# power-supply_pos_v1.net
KiCad netlist of a schematic drawn in EAGLE
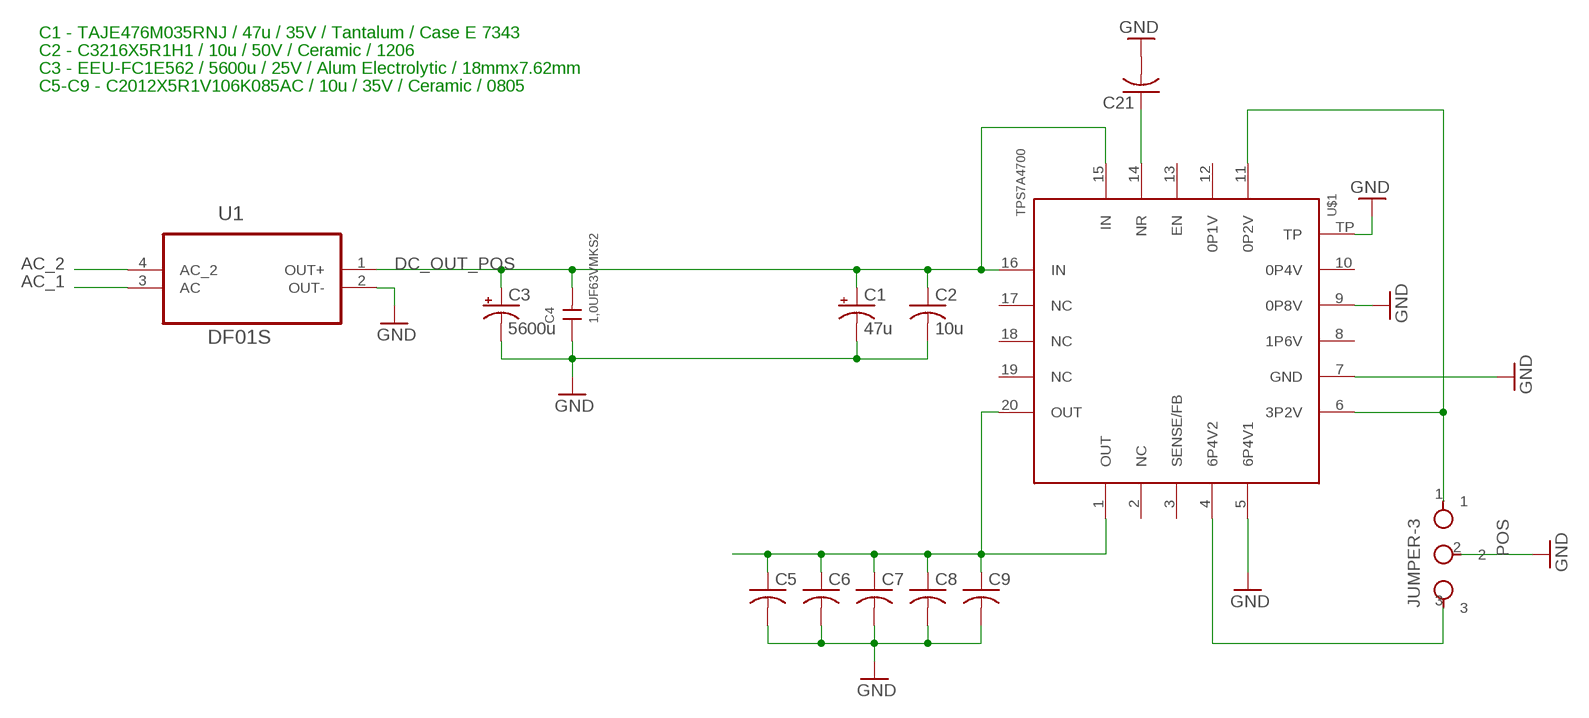
[diagram p0: schematic, sheet 1]
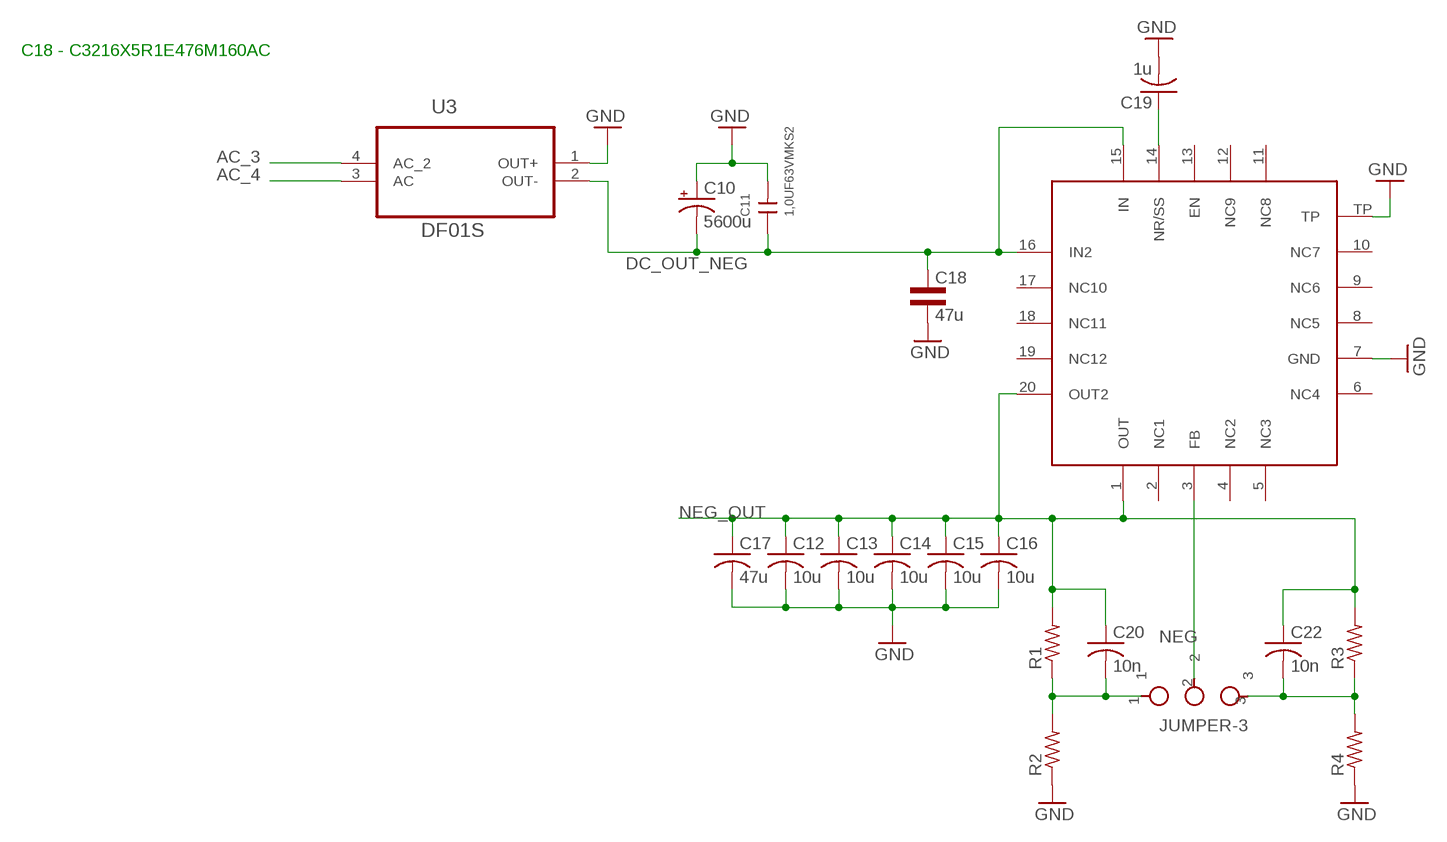
[diagram p1: schematic, sheet 2]

(export (version "E")
  (design (tool "Eeschema 10.0.6"))
  (components
    (comp (ref "C1")
      (value "47u")
      (footprint "eagle-import:SMC_E")
      (libsource (lib "eagle-import") (part "CPOL-USSMCE"))
    )
    (comp (ref "C2")
      (value "10u")
      (footprint "eagle-import:C1206")
      (libsource (lib "eagle-import") (part "C-USC1206"))
    )
    (comp (ref "C3")
      (value "5600u")
      (footprint "eagle-import:E7,5-18")
      (libsource (lib "eagle-import") (part "CPOL-USE7.5-18"))
    )
    (comp (ref "C4")
      (value "1,0UF63VMKS2")
      (footprint "eagle-import:5,0X10,0RM5,0")
      (libsource (lib "eagle-import") (part "1,0UF63VMKS2"))
    )
    (comp (ref "C5")
      (value "C-USC0805")
      (footprint "eagle-import:C0805")
      (libsource (lib "eagle-import") (part "C-USC0805"))
    )
    (comp (ref "C6")
      (value "C-USC0805")
      (footprint "eagle-import:C0805")
      (libsource (lib "eagle-import") (part "C-USC0805"))
    )
    (comp (ref "C7")
      (value "C-USC0805")
      (footprint "eagle-import:C0805")
      (libsource (lib "eagle-import") (part "C-USC0805"))
    )
    (comp (ref "C8")
      (value "C-USC0805")
      (footprint "eagle-import:C0805")
      (libsource (lib "eagle-import") (part "C-USC0805"))
    )
    (comp (ref "C9")
      (value "C-USC0805")
      (footprint "eagle-import:C0805")
      (libsource (lib "eagle-import") (part "C-USC0805"))
    )
    (comp (ref "C21")
      (value "C-USC0603")
      (footprint "eagle-import:C0603")
      (libsource (lib "eagle-import") (part "C-USC0603"))
    )
    (comp (ref "POS")
      (value "JUMPER-3")
      (footprint "eagle-import:1X03")
      (libsource (lib "eagle-import") (part "JUMPER-3"))
    )
    (comp (ref "U$1")
      (value "TPS7A4700")
      (footprint "eagle-import:VQFN-20")
      (libsource (lib "eagle-import") (part "TPS7A4700"))
    )
    (comp (ref "U1")
      (value "DF01S")
      (footprint "eagle-import:SOT508P985X260-4N")
      (libsource (lib "eagle-import") (part "DF01S"))
    )
    (comp (ref "C10")
      (value "5600u")
      (footprint "eagle-import:E7,5-18")
      (libsource (lib "eagle-import") (part "CPOL-USE7.5-18"))
    )
    (comp (ref "C11")
      (value "1,0UF63VMKS2")
      (footprint "eagle-import:5,0X10,0RM5,0")
      (libsource (lib "eagle-import") (part "1,0UF63VMKS2"))
    )
    (comp (ref "C12")
      (value "10u")
      (footprint "eagle-import:C0805")
      (libsource (lib "eagle-import") (part "C-USC0805"))
    )
    (comp (ref "C13")
      (value "10u")
      (footprint "eagle-import:C0805")
      (libsource (lib "eagle-import") (part "C-USC0805"))
    )
    (comp (ref "C14")
      (value "10u")
      (footprint "eagle-import:C0805")
      (libsource (lib "eagle-import") (part "C-USC0805"))
    )
    (comp (ref "C15")
      (value "10u")
      (footprint "eagle-import:C0805")
      (libsource (lib "eagle-import") (part "C-USC0805"))
    )
    (comp (ref "C16")
      (value "10u")
      (footprint "eagle-import:C0805")
      (libsource (lib "eagle-import") (part "C-USC0805"))
    )
    (comp (ref "C17")
      (value "47u")
      (footprint "eagle-import:C2220K")
      (libsource (lib "eagle-import") (part "C-USC2220K"))
    )
    (comp (ref "C18")
      (value "47u")
      (footprint "eagle-import:1206L3")
      (libsource (lib "eagle-import") (part "CAP1206L3"))
    )
    (comp (ref "C19")
      (value "1u")
      (footprint "eagle-import:C0603")
      (libsource (lib "eagle-import") (part "C-USC0603"))
    )
    (comp (ref "C20")
      (value "10n")
      (footprint "eagle-import:C0603")
      (libsource (lib "eagle-import") (part "C-USC0603"))
    )
    (comp (ref "C22")
      (value "10n")
      (footprint "eagle-import:C0603")
      (libsource (lib "eagle-import") (part "C-USC0603"))
    )
    (comp (ref "NEG")
      (value "JUMPER-3")
      (footprint "eagle-import:1X03")
      (libsource (lib "eagle-import") (part "JUMPER-3"))
    )
    (comp (ref "R1")
      (value "R-US_R0603")
      (footprint "eagle-import:R0603")
      (libsource (lib "eagle-import") (part "R-US_R0603"))
    )
    (comp (ref "R2")
      (value "R-US_R0603")
      (footprint "eagle-import:R0603")
      (libsource (lib "eagle-import") (part "R-US_R0603"))
    )
    (comp (ref "R3")
      (value "R-US_R0603")
      (footprint "eagle-import:R0603")
      (libsource (lib "eagle-import") (part "R-US_R0603"))
    )
    (comp (ref "R4")
      (value "R-US_R0603")
      (footprint "eagle-import:R0603")
      (libsource (lib "eagle-import") (part "R-US_R0603"))
    )
    (comp (ref "U$2")
      (value "TPS7A3301RGWT")
      (footprint "eagle-import:VQFN-20")
      (libsource (lib "eagle-import") (part "TPS7A3301RGWT"))
    )
    (comp (ref "U3")
      (value "DF01S")
      (footprint "eagle-import:SOT508P985X260-4N")
      (libsource (lib "eagle-import") (part "DF01S"))
    )
  )
  (nets
    (net (code "1") (name "AC_1") (class "Default")
      (node (ref "U1") (pin "3") (pinfunction "AC_3") (pintype "input"))
    )
    (net (code "2") (name "AC_2") (class "Default")
      (node (ref "U1") (pin "4") (pinfunction "AC_2_4") (pintype "input"))
    )
    (net (code "3") (name "AC_3") (class "Default")
      (node (ref "U3") (pin "4") (pinfunction "AC_2_4") (pintype "input"))
    )
    (net (code "4") (name "AC_4") (class "Default")
      (node (ref "U3") (pin "3") (pinfunction "AC_3") (pintype "input"))
    )
    (net (code "5") (name "DC_OUT_NEG") (class "Default")
      (node (ref "C10") (pin "-") (pinfunction "-_-") (pintype "passive"))
      (node (ref "C11") (pin "1") (pinfunction "1_1") (pintype "passive"))
      (node (ref "C18") (pin "1") (pinfunction "1_1") (pintype "bidirectional"))
      (node (ref "U$2") (pin "15") (pinfunction "IN_15") (pintype "bidirectional"))
      (node (ref "U$2") (pin "16") (pinfunction "IN2_16") (pintype "bidirectional"))
      (node (ref "U3") (pin "2") (pinfunction "OUT-_2") (pintype "output"))
    )
    (net (code "6") (name "DC_OUT_POS") (class "Default")
      (node (ref "C1") (pin "+") (pinfunction "+_+") (pintype "passive"))
      (node (ref "C2") (pin "1") (pinfunction "1_1") (pintype "passive"))
      (node (ref "C3") (pin "+") (pinfunction "+_+") (pintype "passive"))
      (node (ref "C4") (pin "2") (pinfunction "2_2") (pintype "passive"))
      (node (ref "U$1") (pin "15") (pinfunction "IN_15") (pintype "bidirectional"))
      (node (ref "U$1") (pin "16") (pinfunction "IN_16") (pintype "bidirectional"))
      (node (ref "U1") (pin "1") (pinfunction "OUT+_1") (pintype "output"))
    )
    (net (code "7") (name "GND") (class "Default")
      (node (ref "C1") (pin "-") (pinfunction "-_-") (pintype "passive"))
      (node (ref "C10") (pin "+") (pinfunction "+_+") (pintype "passive"))
      (node (ref "C11") (pin "2") (pinfunction "2_2") (pintype "passive"))
      (node (ref "C12") (pin "2") (pinfunction "2_2") (pintype "passive"))
      (node (ref "C13") (pin "2") (pinfunction "2_2") (pintype "passive"))
      (node (ref "C14") (pin "2") (pinfunction "2_2") (pintype "passive"))
      (node (ref "C15") (pin "2") (pinfunction "2_2") (pintype "passive"))
      (node (ref "C16") (pin "2") (pinfunction "2_2") (pintype "passive"))
      (node (ref "C17") (pin "2") (pinfunction "2_2") (pintype "passive"))
      (node (ref "C18") (pin "2") (pinfunction "2_2") (pintype "bidirectional"))
      (node (ref "C19") (pin "2") (pinfunction "2_2") (pintype "passive"))
      (node (ref "C2") (pin "2") (pinfunction "2_2") (pintype "passive"))
      (node (ref "C21") (pin "2") (pinfunction "2_2") (pintype "passive"))
      (node (ref "C3") (pin "-") (pinfunction "-_-") (pintype "passive"))
      (node (ref "C4") (pin "1") (pinfunction "1_1") (pintype "passive"))
      (node (ref "C5") (pin "2") (pinfunction "2_2") (pintype "passive"))
      (node (ref "C6") (pin "2") (pinfunction "2_2") (pintype "passive"))
      (node (ref "C7") (pin "2") (pinfunction "2_2") (pintype "passive"))
      (node (ref "C8") (pin "2") (pinfunction "2_2") (pintype "passive"))
      (node (ref "C9") (pin "2") (pinfunction "2_2") (pintype "passive"))
      (node (ref "POS") (pin "2") (pinfunction "2_2") (pintype "bidirectional"))
      (node (ref "R2") (pin "1") (pinfunction "1_1") (pintype "passive"))
      (node (ref "R4") (pin "1") (pinfunction "1_1") (pintype "passive"))
      (node (ref "U$1") (pin "5") (pinfunction "6P4V1_5") (pintype "bidirectional"))
      (node (ref "U$1") (pin "7") (pinfunction "GND_7") (pintype "bidirectional"))
      (node (ref "U$1") (pin "9") (pinfunction "0P8V_9") (pintype "bidirectional"))
      (node (ref "U$1") (pin "TP") (pinfunction "TP_TP") (pintype "bidirectional"))
      (node (ref "U$2") (pin "7") (pinfunction "GND_7") (pintype "bidirectional"))
      (node (ref "U$2") (pin "TP") (pinfunction "TP_TP") (pintype "bidirectional"))
      (node (ref "U1") (pin "2") (pinfunction "OUT-_2") (pintype "output"))
      (node (ref "U3") (pin "1") (pinfunction "OUT+_1") (pintype "output"))
    )
    (net (code "8") (name "NEG_OUT") (class "Default")
      (node (ref "C12") (pin "1") (pinfunction "1_1") (pintype "passive"))
      (node (ref "C13") (pin "1") (pinfunction "1_1") (pintype "passive"))
      (node (ref "C14") (pin "1") (pinfunction "1_1") (pintype "passive"))
      (node (ref "C15") (pin "1") (pinfunction "1_1") (pintype "passive"))
      (node (ref "C16") (pin "1") (pinfunction "1_1") (pintype "passive"))
      (node (ref "C17") (pin "1") (pinfunction "1_1") (pintype "passive"))
      (node (ref "C20") (pin "1") (pinfunction "1_1") (pintype "passive"))
      (node (ref "C22") (pin "1") (pinfunction "1_1") (pintype "passive"))
      (node (ref "R1") (pin "2") (pinfunction "2_2") (pintype "passive"))
      (node (ref "R3") (pin "2") (pinfunction "2_2") (pintype "passive"))
      (node (ref "U$2") (pin "1") (pinfunction "OUT_1") (pintype "bidirectional"))
      (node (ref "U$2") (pin "20") (pinfunction "OUT2_20") (pintype "bidirectional"))
    )
    (net (code "9") (name "Net-(C5-Pad1)") (class "Default")
      (node (ref "C5") (pin "1") (pinfunction "1_1") (pintype "passive"))
      (node (ref "C6") (pin "1") (pinfunction "1_1") (pintype "passive"))
      (node (ref "C7") (pin "1") (pinfunction "1_1") (pintype "passive"))
      (node (ref "C8") (pin "1") (pinfunction "1_1") (pintype "passive"))
      (node (ref "C9") (pin "1") (pinfunction "1_1") (pintype "passive"))
      (node (ref "U$1") (pin "1") (pinfunction "OUT_1") (pintype "bidirectional"))
      (node (ref "U$1") (pin "20") (pinfunction "OUT_20") (pintype "bidirectional"))
    )
    (net (code "10") (name "Net-(C20-Pad2)") (class "Default")
      (node (ref "C20") (pin "2") (pinfunction "2_2") (pintype "passive"))
      (node (ref "NEG") (pin "1") (pinfunction "1_1") (pintype "bidirectional"))
      (node (ref "R1") (pin "1") (pinfunction "1_1") (pintype "passive"))
      (node (ref "R2") (pin "2") (pinfunction "2_2") (pintype "passive"))
    )
    (net (code "11") (name "Net-(C22-Pad2)") (class "Default")
      (node (ref "C22") (pin "2") (pinfunction "2_2") (pintype "passive"))
      (node (ref "NEG") (pin "3") (pinfunction "3_3") (pintype "bidirectional"))
      (node (ref "R3") (pin "1") (pinfunction "1_1") (pintype "passive"))
      (node (ref "R4") (pin "2") (pinfunction "2_2") (pintype "passive"))
    )
    (net (code "12") (name "Net-(U$1-0P2V)") (class "Default")
      (node (ref "POS") (pin "1") (pinfunction "1_1") (pintype "bidirectional"))
      (node (ref "U$1") (pin "11") (pinfunction "0P2V_11") (pintype "bidirectional"))
      (node (ref "U$1") (pin "6") (pinfunction "3P2V_6") (pintype "bidirectional"))
    )
    (net (code "13") (name "Net-(U$1-6P4V2)") (class "Default")
      (node (ref "POS") (pin "3") (pinfunction "3_3") (pintype "bidirectional"))
      (node (ref "U$1") (pin "4") (pinfunction "6P4V2_4") (pintype "bidirectional"))
    )
    (net (code "14") (name "Net-(U$1-NR)") (class "Default")
      (node (ref "C21") (pin "1") (pinfunction "1_1") (pintype "passive"))
      (node (ref "U$1") (pin "14") (pinfunction "NR_14") (pintype "bidirectional"))
    )
    (net (code "15") (name "Net-(U$2-FB)") (class "Default")
      (node (ref "NEG") (pin "2") (pinfunction "2_2") (pintype "bidirectional"))
      (node (ref "U$2") (pin "3") (pinfunction "FB_3") (pintype "bidirectional"))
    )
    (net (code "16") (name "Net-(U$2-NR{slash}SS)") (class "Default")
      (node (ref "C19") (pin "1") (pinfunction "1_1") (pintype "passive"))
      (node (ref "U$2") (pin "14") (pinfunction "NR/SS_14") (pintype "bidirectional"))
    )
    (net (code "17") (name "unconnected-(U$1-0P1V-Pad12)") (class "Default")
      (node (ref "U$1") (pin "12") (pinfunction "0P1V_12") (pintype "bidirectional"))
    )
    (net (code "18") (name "unconnected-(U$1-0P4V-Pad10)") (class "Default")
      (node (ref "U$1") (pin "10") (pinfunction "0P4V_10") (pintype "bidirectional"))
    )
    (net (code "19") (name "unconnected-(U$1-1P6V-Pad8)") (class "Default")
      (node (ref "U$1") (pin "8") (pinfunction "1P6V_8") (pintype "bidirectional"))
    )
    (net (code "20") (name "unconnected-(U$1-EN-Pad13)") (class "Default")
      (node (ref "U$1") (pin "13") (pinfunction "EN_13") (pintype "bidirectional"))
    )
    (net (code "21") (name "unconnected-(U$1-NC-Pad2)") (class "Default")
      (node (ref "U$1") (pin "2") (pinfunction "NC_2") (pintype "bidirectional"))
    )
    (net (code "22") (name "unconnected-(U$1-NC-Pad17)") (class "Default")
      (node (ref "U$1") (pin "17") (pinfunction "NC_17") (pintype "bidirectional"))
    )
    (net (code "23") (name "unconnected-(U$1-NC-Pad18)") (class "Default")
      (node (ref "U$1") (pin "18") (pinfunction "NC_18") (pintype "bidirectional"))
    )
    (net (code "24") (name "unconnected-(U$1-NC-Pad19)") (class "Default")
      (node (ref "U$1") (pin "19") (pinfunction "NC_19") (pintype "bidirectional"))
    )
    (net (code "25") (name "unconnected-(U$1-SENSE{slash}FB-Pad3)") (class "Default")
      (node (ref "U$1") (pin "3") (pinfunction "SENSE/FB_3") (pintype "bidirectional"))
    )
    (net (code "26") (name "unconnected-(U$2-EN-Pad13)") (class "Default")
      (node (ref "U$2") (pin "13") (pinfunction "EN_13") (pintype "bidirectional"))
    )
    (net (code "27") (name "unconnected-(U$2-NC1-Pad2)") (class "Default")
      (node (ref "U$2") (pin "2") (pinfunction "NC1_2") (pintype "bidirectional"))
    )
    (net (code "28") (name "unconnected-(U$2-NC2-Pad4)") (class "Default")
      (node (ref "U$2") (pin "4") (pinfunction "NC2_4") (pintype "bidirectional"))
    )
    (net (code "29") (name "unconnected-(U$2-NC3-Pad5)") (class "Default")
      (node (ref "U$2") (pin "5") (pinfunction "NC3_5") (pintype "bidirectional"))
    )
    (net (code "30") (name "unconnected-(U$2-NC4-Pad6)") (class "Default")
      (node (ref "U$2") (pin "6") (pinfunction "NC4_6") (pintype "bidirectional"))
    )
    (net (code "31") (name "unconnected-(U$2-NC5-Pad8)") (class "Default")
      (node (ref "U$2") (pin "8") (pinfunction "NC5_8") (pintype "bidirectional"))
    )
    (net (code "32") (name "unconnected-(U$2-NC6-Pad9)") (class "Default")
      (node (ref "U$2") (pin "9") (pinfunction "NC6_9") (pintype "bidirectional"))
    )
    (net (code "33") (name "unconnected-(U$2-NC7-Pad10)") (class "Default")
      (node (ref "U$2") (pin "10") (pinfunction "NC7_10") (pintype "bidirectional"))
    )
    (net (code "34") (name "unconnected-(U$2-NC8-Pad11)") (class "Default")
      (node (ref "U$2") (pin "11") (pinfunction "NC8_11") (pintype "bidirectional"))
    )
    (net (code "35") (name "unconnected-(U$2-NC9-Pad12)") (class "Default")
      (node (ref "U$2") (pin "12") (pinfunction "NC9_12") (pintype "bidirectional"))
    )
    (net (code "36") (name "unconnected-(U$2-NC10-Pad17)") (class "Default")
      (node (ref "U$2") (pin "17") (pinfunction "NC10_17") (pintype "bidirectional"))
    )
    (net (code "37") (name "unconnected-(U$2-NC11-Pad18)") (class "Default")
      (node (ref "U$2") (pin "18") (pinfunction "NC11_18") (pintype "bidirectional"))
    )
    (net (code "38") (name "unconnected-(U$2-NC12-Pad19)") (class "Default")
      (node (ref "U$2") (pin "19") (pinfunction "NC12_19") (pintype "bidirectional"))
    )
  )
)
